# SCH_Freematics_ONE.net
KiCad netlist of a schematic drawn in Altium Designer
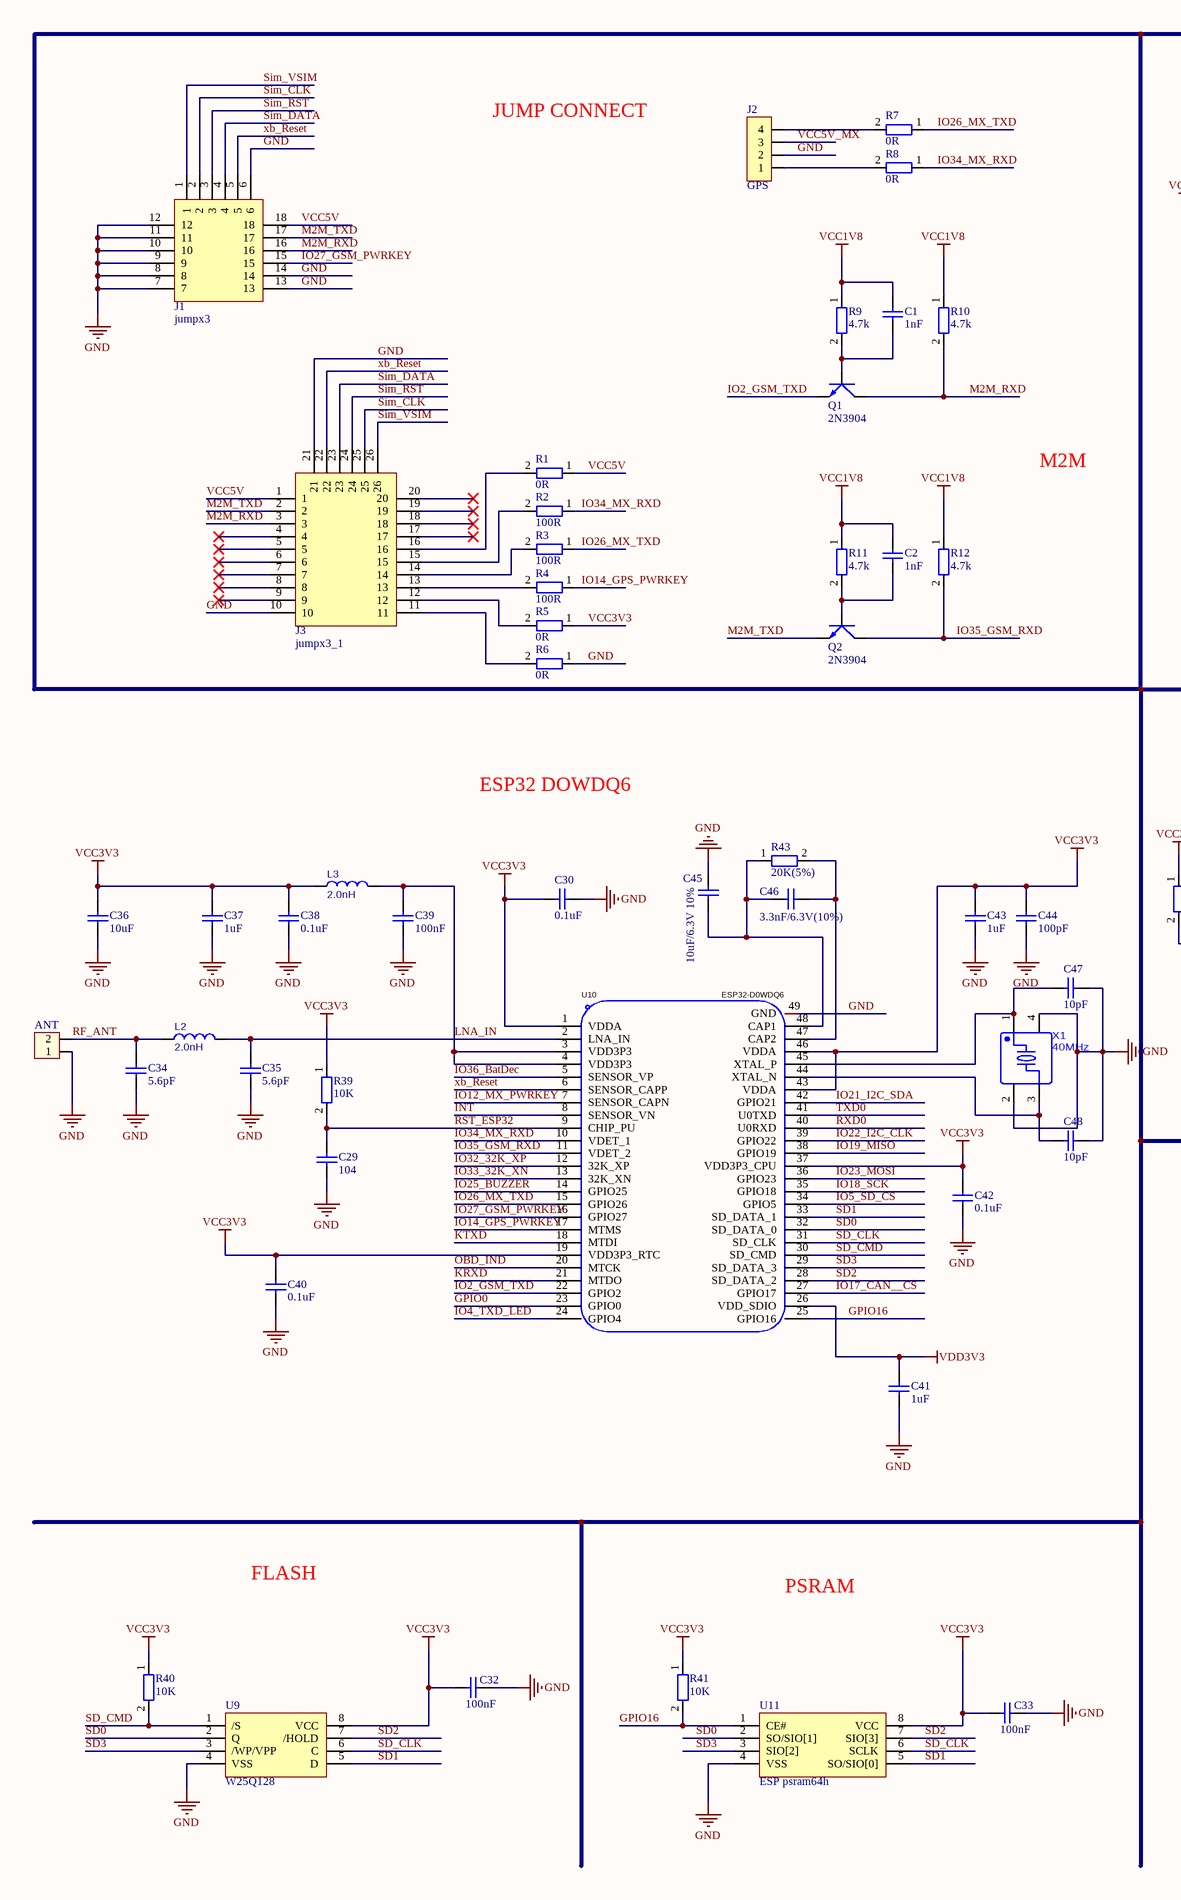
[diagram p0: SCH_Freematics_ONE.SchDoc, left]
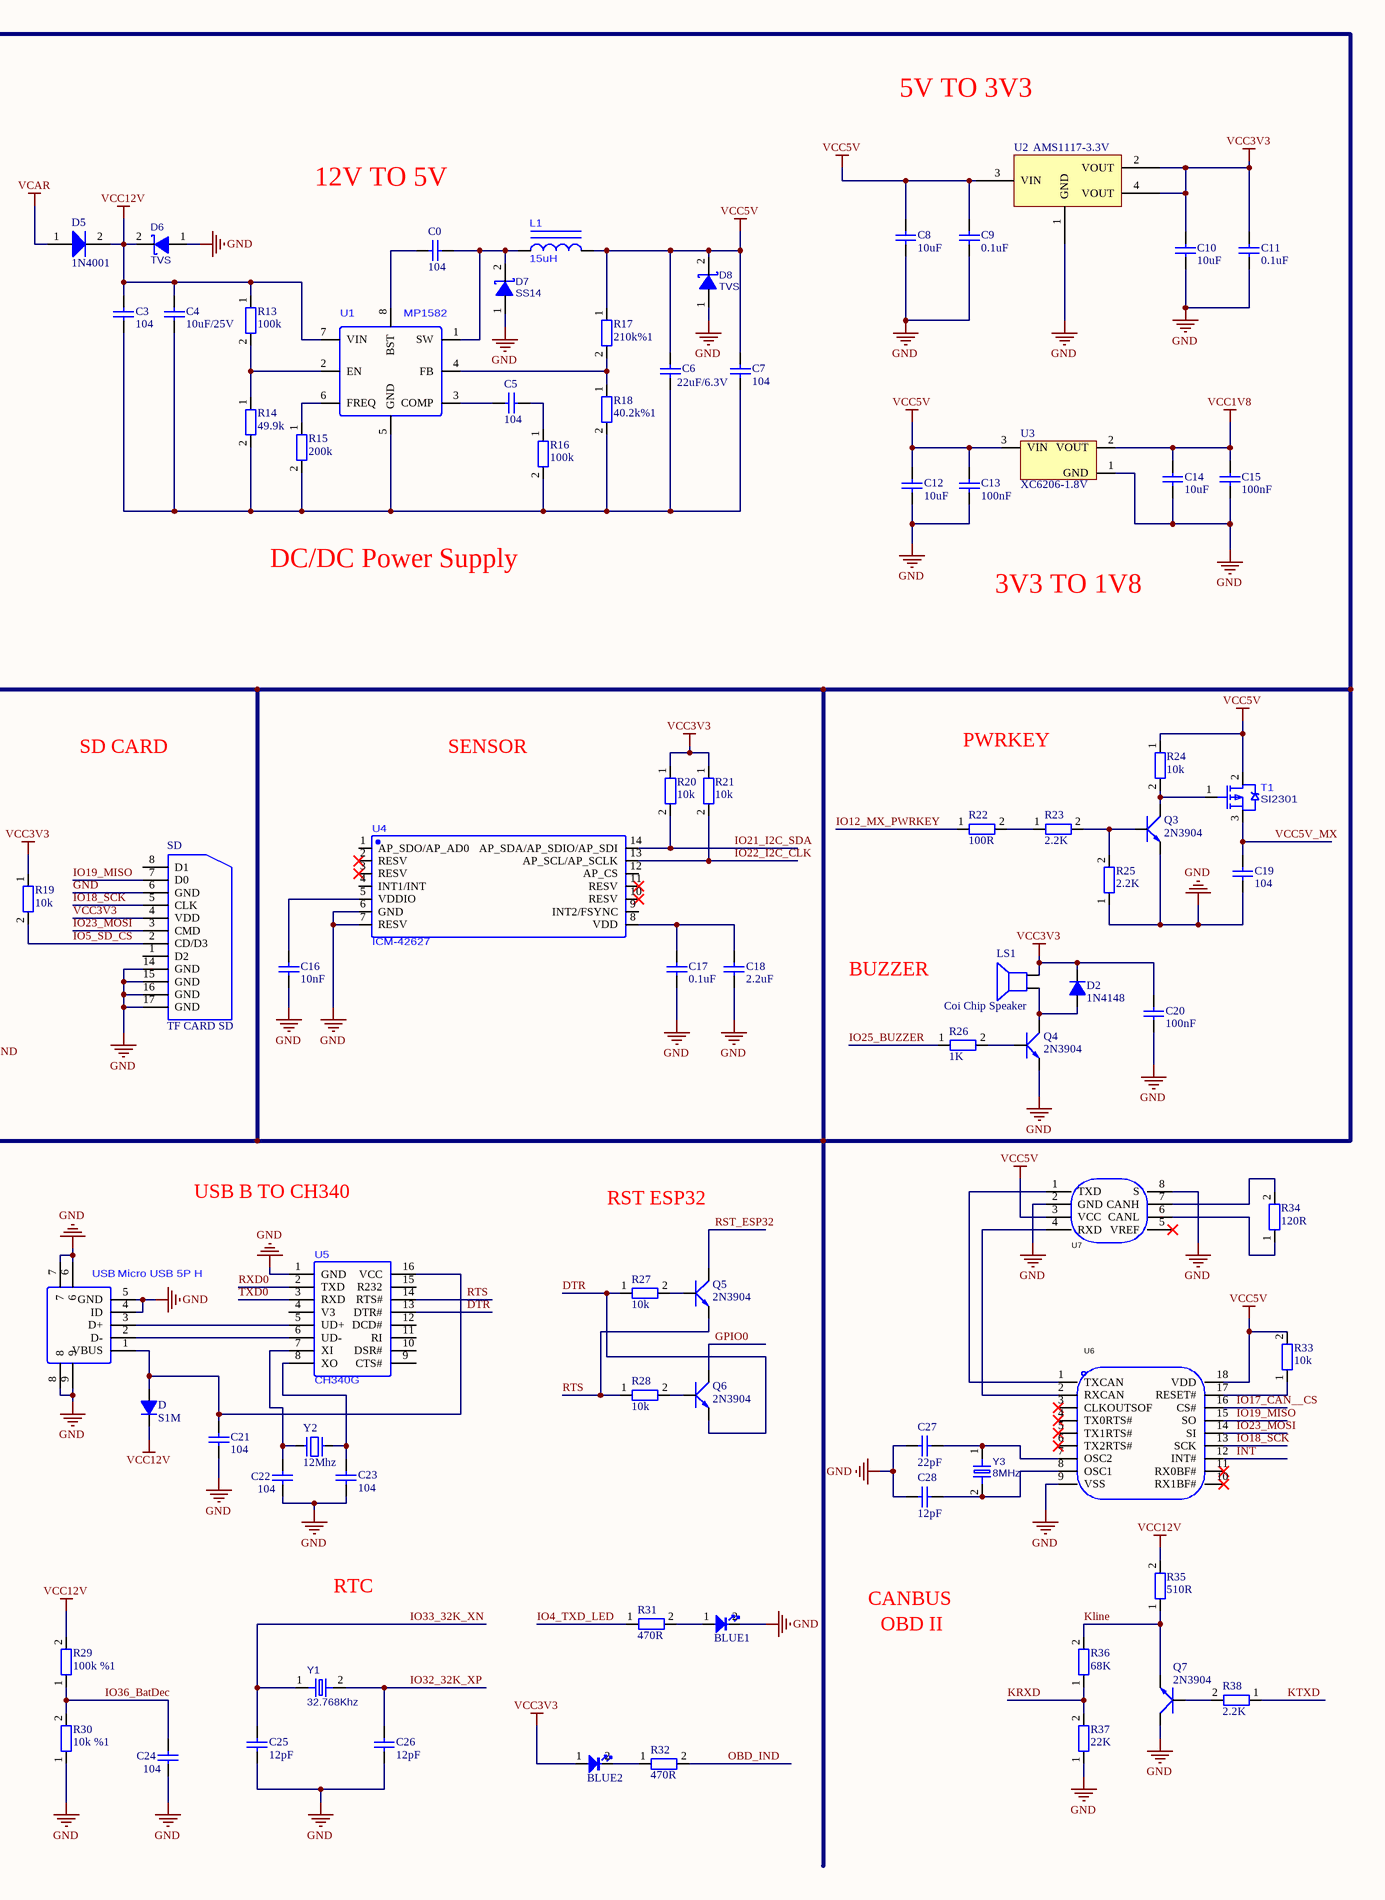
[diagram p1: SCH_Freematics_ONE.SchDoc, right]

(export (version "E")
  (design (tool "Eeschema 10.0.6"))
  (components
    (comp (ref "ANT")
      (value "Header 2")
      (footprint "HED2T")
      (description "Header 2 (Green)")
      (libsource (lib "SCH_Library") (part "Hed2"))
    )
    (comp (ref "BLUE1")
      (value "LED")
      (footprint "LED 0603")
      (description "Emerald 0603 Light Emitting Diodes (LED) ROHS")
      (libsource (lib "SCH_Library") (part "LED SMD 0603"))
    )
    (comp (ref "BLUE2")
      (value "LED")
      (footprint "LED 0603")
      (description "Emerald 0603 Light Emitting Diodes (LED) ROHS")
      (libsource (lib "SCH_Library") (part "LED SMD 0603"))
    )
    (comp (ref "C0")
      (value "104")
      (footprint "CAP0201")
      (description "Capacitor")
      (libsource (lib "SCH_Library") (part "CAP104-100nF-50V"))
    )
    (comp (ref "C1")
      (value "1nF")
      (footprint "CAP0201")
      (description "Capacitor")
      (libsource (lib "SCH_Library") (part "CAP104-100nF-50V"))
    )
    (comp (ref "C2")
      (value "1nF")
      (footprint "CAP0201")
      (description "Capacitor")
      (libsource (lib "SCH_Library") (part "CAP104-100nF-50V"))
    )
    (comp (ref "C3")
      (value "104")
      (footprint "CAP0201")
      (description "Capacitor")
      (libsource (lib "SCH_Library") (part "CAP104-100nF-50V"))
    )
    (comp (ref "C4")
      (value "10uF/25V")
      (footprint "CAP0201")
      (description "Capacitor")
      (libsource (lib "SCH_Library") (part "CAP104-100nF-50V"))
    )
    (comp (ref "C5")
      (value "104")
      (footprint "CAP0201")
      (description "Capacitor")
      (libsource (lib "SCH_Library") (part "CAP104-100nF-50V"))
    )
    (comp (ref "C6")
      (value "22uF/6.3V")
      (footprint "CAP0201")
      (description "Capacitor")
      (libsource (lib "SCH_Library") (part "CAP104-100nF-50V"))
    )
    (comp (ref "C7")
      (value "104")
      (footprint "CAP0201")
      (description "Capacitor")
      (libsource (lib "SCH_Library") (part "CAP104-100nF-50V"))
    )
    (comp (ref "C8")
      (value "10uF")
      (footprint "CAP0201")
      (description "0805 Multilayer Ceramic Capacitors MLCC - SMD/SMT ROHS")
      (libsource (lib "SCH_AES_Library") (part "CAP 0805 50V 10%"))
    )
    (comp (ref "C9")
      (value "0.1uF")
      (footprint "CAP0201")
      (description "0805 Multilayer Ceramic Capacitors MLCC - SMD/SMT ROHS")
      (libsource (lib "SCH_AES_Library") (part "CAP 0805 50V 10%"))
    )
    (comp (ref "C10")
      (value "10uF")
      (footprint "CAP0201")
      (description "0805 Multilayer Ceramic Capacitors MLCC - SMD/SMT ROHS")
      (libsource (lib "SCH_AES_Library") (part "CAP 0805 50V 10%"))
    )
    (comp (ref "C11")
      (value "0.1uF")
      (footprint "CAP0201")
      (description "0805 Multilayer Ceramic Capacitors MLCC - SMD/SMT ROHS")
      (libsource (lib "SCH_AES_Library") (part "CAP 0805 50V 10%"))
    )
    (comp (ref "C12")
      (value "10uF")
      (footprint "CAP0201")
      (description "Capacitor")
      (libsource (lib "SCH_Library") (part "CAP104-100nF-50V"))
    )
    (comp (ref "C13")
      (value "100nF")
      (footprint "CAP0201")
      (description "Capacitor")
      (libsource (lib "SCH_Library") (part "CAP104-100nF-50V"))
    )
    (comp (ref "C14")
      (value "10uF")
      (footprint "CAP0201")
      (description "Capacitor")
      (libsource (lib "SCH_Library") (part "CAP104-100nF-50V"))
    )
    (comp (ref "C15")
      (value "100nF")
      (footprint "CAP0201")
      (description "Capacitor")
      (libsource (lib "SCH_Library") (part "CAP104-100nF-50V"))
    )
    (comp (ref "C16")
      (value "10nF")
      (footprint "CAP0201")
      (description "Capacitor")
      (libsource (lib "SCH_Library") (part "CAP104-100nF-50V"))
    )
    (comp (ref "C17")
      (value "0.1uF")
      (footprint "CAP0201")
      (description "Capacitor")
      (libsource (lib "SCH_Library") (part "CAP104-100nF-50V"))
    )
    (comp (ref "C18")
      (value "2.2uF")
      (footprint "CAP0201")
      (description "Capacitor")
      (libsource (lib "SCH_Library") (part "CAP104-100nF-50V"))
    )
    (comp (ref "C19")
      (value "104")
      (footprint "CAP0201")
      (description "Capacitor")
      (libsource (lib "SCH_Library") (part "CAP104-100nF-50V"))
    )
    (comp (ref "C20")
      (value "100nF")
      (footprint "CAP0201")
      (description "Capacitor")
      (libsource (lib "SCH_Library") (part "CAP104-100nF-50V"))
    )
    (comp (ref "C21")
      (value "104")
      (footprint "CAP0201")
      (description "Capacitor")
      (libsource (lib "SCH_Library") (part "CAP104-100nF-50V"))
    )
    (comp (ref "C22")
      (value "104")
      (footprint "CAP0201")
      (description "Capacitor")
      (libsource (lib "SCH_Library") (part "CAP104-100nF-50V"))
    )
    (comp (ref "C23")
      (value "104")
      (footprint "CAP0201")
      (description "Capacitor")
      (libsource (lib "SCH_Library") (part "CAP104-100nF-50V"))
    )
    (comp (ref "C24")
      (value "104")
      (footprint "CAP0201")
      (description "Capacitor")
      (libsource (lib "SCH_Library") (part "CAP104-100nF-50V"))
    )
    (comp (ref "C25")
      (value "12pF")
      (footprint "CAP0201")
      (description "Capacitor")
      (libsource (lib "SCH_Library") (part "CAP104-100nF-50V"))
    )
    (comp (ref "C26")
      (value "12pF")
      (footprint "CAP0201")
      (description "Capacitor")
      (libsource (lib "SCH_Library") (part "CAP104-100nF-50V"))
    )
    (comp (ref "C27")
      (value "22pF")
      (footprint "CAP0201")
      (description "Capacitor")
      (libsource (lib "SCH_Library") (part "CAP104-100nF-50V"))
    )
    (comp (ref "C28")
      (value "12pF")
      (footprint "CAP0201")
      (description "Capacitor")
      (libsource (lib "SCH_Library") (part "CAP104-100nF-50V"))
    )
    (comp (ref "C29")
      (value "104")
      (footprint "CAP0201")
      (description "Capacitor")
      (libsource (lib "SCH_Library") (part "CAP104-100nF-50V"))
    )
    (comp (ref "C30")
      (value "0.1uF")
      (footprint "CAP0201")
      (description "Capacitor")
      (libsource (lib "SCH_Library") (part "CAP104-100nF-50V"))
    )
    (comp (ref "C32")
      (value "100nF")
      (footprint "CAP0201")
      (description "Capacitor")
      (libsource (lib "SCH_Library") (part "CAP104-100nF-50V"))
    )
    (comp (ref "C33")
      (value "100nF")
      (footprint "CAP0201")
      (description "Capacitor")
      (libsource (lib "SCH_Library") (part "CAP104-100nF-50V"))
    )
    (comp (ref "C34")
      (value "5.6pF")
      (footprint "CAP0201")
      (description "Capacitor")
      (libsource (lib "SCH_Library") (part "CAP104-100nF-50V"))
    )
    (comp (ref "C35")
      (value "5.6pF")
      (footprint "CAP0201")
      (description "Capacitor")
      (libsource (lib "SCH_Library") (part "CAP104-100nF-50V"))
    )
    (comp (ref "C36")
      (value "10uF")
      (footprint "CAP0201")
      (description "Capacitor")
      (libsource (lib "SCH_Library") (part "CAP104-100nF-50V"))
    )
    (comp (ref "C37")
      (value "1uF")
      (footprint "CAP0201")
      (description "Capacitor")
      (libsource (lib "SCH_Library") (part "CAP104-100nF-50V"))
    )
    (comp (ref "C38")
      (value "0.1uF")
      (footprint "CAP0201")
      (description "Capacitor")
      (libsource (lib "SCH_Library") (part "CAP104-100nF-50V"))
    )
    (comp (ref "C39")
      (value "100nF")
      (footprint "CAP0201")
      (description "Capacitor")
      (libsource (lib "SCH_Library") (part "CAP104-100nF-50V"))
    )
    (comp (ref "C40")
      (value "0.1uF")
      (footprint "CAP0201")
      (description "Capacitor")
      (libsource (lib "SCH_Library") (part "CAP104-100nF-50V"))
    )
    (comp (ref "C41")
      (value "1uF")
      (footprint "CAP0201")
      (description "Capacitor")
      (libsource (lib "SCH_Library") (part "CAP104-100nF-50V"))
    )
    (comp (ref "C42")
      (value "0.1uF")
      (footprint "CAP0201")
      (description "Capacitor")
      (libsource (lib "SCH_Library") (part "CAP104-100nF-50V"))
    )
    (comp (ref "C43")
      (value "1uF")
      (footprint "CAP0201")
      (description "Capacitor")
      (libsource (lib "SCH_Library") (part "CAP104-100nF-50V"))
    )
    (comp (ref "C44")
      (value "100pF")
      (footprint "CAP0201")
      (description "Capacitor")
      (libsource (lib "SCH_Library") (part "CAP104-100nF-50V"))
    )
    (comp (ref "C45")
      (value "10uF/6.3V 10%")
      (footprint "CAP_0805")
      (description "Capacitor")
      (libsource (lib "SCH_Library") (part "CAP104-100nF-50V"))
    )
    (comp (ref "C46")
      (value "3.3nF/6.3V(10%)")
      (footprint "CAP0201")
      (description "Capacitor")
      (libsource (lib "SCH_Library") (part "CAP104-100nF-50V"))
    )
    (comp (ref "C47")
      (value "10pF")
      (footprint "CAP0201")
      (description "Capacitor")
      (libsource (lib "SCH_Library") (part "CAP104-100nF-50V"))
    )
    (comp (ref "C48")
      (value "10pF")
      (footprint "CAP0201")
      (description "Capacitor")
      (libsource (lib "SCH_Library") (part "CAP104-100nF-50V"))
    )
    (comp (ref "D")
      (value "S1M")
      (footprint "DIODE_M7_1N4007")
      (description "Diode 1A")
      (libsource (lib "SCH_Library") (part "1N5819W"))
    )
    (comp (ref "D2")
      (value "1N4148")
      (footprint "DIODE_M7_1N4007")
      (description "Diode 1A")
      (libsource (lib "SCH_Library") (part "D1A"))
    )
    (comp (ref "D5")
      (value "1N4001")
      (footprint "Diode HOLD STAND DO-41 TYPE 1A")
      (description "1A 1kV Diodes - General Purpose ROHS")
      (libsource (lib "SCH_Library") (part "DIODE SMD 1N4007"))
    )
    (comp (ref "D6")
      (value "TVS")
      (footprint "DO-214AC(SMA)")
      (description "500uA@40V 40V 550mV@5A 5A SMA(DO-214AC) Schottky Barrier Diodes (SBD) ROHS")
      (fields
        (field (name "BOM_SUPPLIER PART") "C478723")
        (field (name "BOM_MANUFACTURER PART") "SS34")
        (field (name "CONTRIBUTOR") "LCSC")
      )
      (libsource (lib "SCH_Library") (part "DIODE SMD SS54"))
    )
    (comp (ref "D7")
      (value "SS14")
      (footprint "DO-214AC(SMA)")
      (description "500uA@40V 40V 550mV@5A 5A SMA(DO-214AC) Schottky Barrier Diodes (SBD) ROHS")
      (fields
        (field (name "BOM_SUPPLIER PART") "C478723")
        (field (name "BOM_MANUFACTURER PART") "SS34")
        (field (name "CONTRIBUTOR") "LCSC")
      )
      (libsource (lib "SCH_Library") (part "DIODE SMD SS54"))
    )
    (comp (ref "D8")
      (value "TVS")
      (footprint "DO-214AC(SMA)")
      (description "500uA@40V 40V 550mV@5A 5A SMA(DO-214AC) Schottky Barrier Diodes (SBD) ROHS")
      (fields
        (field (name "BOM_SUPPLIER PART") "C478723")
        (field (name "BOM_MANUFACTURER PART") "SS34")
        (field (name "CONTRIBUTOR") "LCSC")
      )
      (libsource (lib "SCH_Library") (part "DIODE SMD SS54"))
    )
    (comp (ref "J1") (value "jumpx3") (libsource (lib "SCH_Library") (part "jumpx3")))
    (comp (ref "J2")
      (value "GPS")
      (footprint "JP 1x4 DT")
      (description "Cắm")
      (libsource (lib "Altium_Lib") (part "JP 1x4 2.54 Duc Thang"))
    )
    (comp (ref "J3") (value "jumpx3_1") (libsource (lib "SCH_Library") (part "jumpx3_1")))
    (comp (ref "L1") (value "15uH") (libsource (lib "SCH_Library") (part "Inductor")))
    (comp (ref "L2")
      (value "2.0nH")
      (footprint "INDUCTOR_0201")
      (fields
        (field (name "BOM_SUPPLIER PART") "C578001")
        (field (name "BOM_MANUFACTURER PART") "SCHF160808H47NJT")
        (field (name "CONTRIBUTOR") "LCSC")
      )
      (libsource (lib "SCH_Library") (part "INDUCTORS SMD"))
    )
    (comp (ref "L3")
      (value "2.0nH")
      (footprint "INDUCTOR_0201")
      (fields
        (field (name "BOM_SUPPLIER PART") "C578001")
        (field (name "BOM_MANUFACTURER PART") "SCHF160808H47NJT")
        (field (name "CONTRIBUTOR") "LCSC")
      )
      (libsource (lib "SCH_Library") (part "INDUCTORS SMD"))
    )
    (comp (ref "LS1")
      (value "Coi Chip Speaker")
      (footprint "Coi Chip Speacker")
      (description "Còi chip")
      (libsource (lib "SCH_Library") (part "Coi Chip Speaker"))
    )
    (comp (ref "Q1")
      (value "2N3904")
      (footprint "SOT-23")
      (description "SOT-23 - C8658")
      (libsource (lib "Altium_Lib") (part "Trans BC817"))
    )
    (comp (ref "Q2")
      (value "2N3904")
      (footprint "SOT-23")
      (description "SOT-23 - C8658")
      (libsource (lib "Altium_Lib") (part "Trans BC817"))
    )
    (comp (ref "Q3")
      (value "2N3904")
      (footprint "SOT-23")
      (description "SOT-23 - C8658")
      (libsource (lib "Altium_Lib") (part "Trans BC817"))
    )
    (comp (ref "Q4")
      (value "2N3904")
      (footprint "SOT-23")
      (description "SOT-23 - C8658")
      (libsource (lib "Altium_Lib") (part "Trans BC817"))
    )
    (comp (ref "Q5")
      (value "2N3904")
      (footprint "SOT-23")
      (description "SOT-23 - C8658")
      (libsource (lib "Altium_Lib") (part "Trans BC817"))
    )
    (comp (ref "Q6")
      (value "2N3904")
      (footprint "SOT-23")
      (description "SOT-23 - C8658")
      (libsource (lib "Altium_Lib") (part "Trans BC817"))
    )
    (comp (ref "Q7")
      (value "2N3904")
      (footprint "SOT-23")
      (description "SOT-23 - C8658")
      (libsource (lib "Altium_Lib") (part "Trans BC817"))
    )
    (comp (ref "R1")
      (value "0R")
      (footprint "RESC0201_L")
      (description "±1% - Chip Resistor - Surface Mount ROHS")
      (libsource (lib "SCH_Library") (part "RES 0603 1%_"))
    )
    (comp (ref "R2")
      (value "100R")
      (footprint "RESC0201_L")
      (description "±1% - Chip Resistor - Surface Mount ROHS")
      (libsource (lib "SCH_Library") (part "RES 0603 1%_"))
    )
    (comp (ref "R3")
      (value "100R")
      (footprint "RESC0201_L")
      (description "±1% - Chip Resistor - Surface Mount ROHS")
      (libsource (lib "SCH_Library") (part "RES 0603 1%_"))
    )
    (comp (ref "R4")
      (value "100R")
      (footprint "RESC0201_L")
      (description "±1% - Chip Resistor - Surface Mount ROHS")
      (libsource (lib "SCH_Library") (part "RES 0603 1%_"))
    )
    (comp (ref "R5")
      (value "0R")
      (footprint "RESC0201_L")
      (description "±1% - Chip Resistor - Surface Mount ROHS")
      (libsource (lib "SCH_Library") (part "RES 0603 1%_"))
    )
    (comp (ref "R6")
      (value "0R")
      (footprint "RESC0201_L")
      (description "±1% - Chip Resistor - Surface Mount ROHS")
      (libsource (lib "SCH_Library") (part "RES 0603 1%_"))
    )
    (comp (ref "R7")
      (value "0R")
      (footprint "RESC0201_L")
      (description "±1% - Chip Resistor - Surface Mount ROHS")
      (libsource (lib "SCH_Library") (part "RES 0603 1%_"))
    )
    (comp (ref "R8")
      (value "0R")
      (footprint "RESC0201_L")
      (description "±1% - Chip Resistor - Surface Mount ROHS")
      (libsource (lib "SCH_Library") (part "RES 0603 1%_"))
    )
    (comp (ref "R9")
      (value "4.7k")
      (footprint "RESC0201_L")
      (description "±1% - Chip Resistor - Surface Mount ROHS")
      (libsource (lib "SCH_Library") (part "RES 0603 1%_"))
    )
    (comp (ref "R10")
      (value "4.7k")
      (footprint "RESC0201_L")
      (description "±1% - Chip Resistor - Surface Mount ROHS")
      (libsource (lib "SCH_Library") (part "RES 0603 1%_"))
    )
    (comp (ref "R11")
      (value "4.7k")
      (footprint "RESC0201_L")
      (description "±1% - Chip Resistor - Surface Mount ROHS")
      (libsource (lib "SCH_Library") (part "RES 0603 1%_"))
    )
    (comp (ref "R12")
      (value "4.7k")
      (footprint "RESC0201_L")
      (description "±1% - Chip Resistor - Surface Mount ROHS")
      (libsource (lib "SCH_Library") (part "RES 0603 1%_"))
    )
    (comp (ref "R13")
      (value "100k")
      (footprint "RESC0201_L")
      (description "±1% - Chip Resistor - Surface Mount ROHS")
      (libsource (lib "SCH_Library") (part "RES 0603 1%_"))
    )
    (comp (ref "R14")
      (value "49.9k")
      (footprint "RESC0201_L")
      (description "±1% - Chip Resistor - Surface Mount ROHS")
      (libsource (lib "SCH_Library") (part "RES 0603 1%_"))
    )
    (comp (ref "R15")
      (value "200k")
      (footprint "RESC0201_L")
      (description "±1% - Chip Resistor - Surface Mount ROHS")
      (libsource (lib "SCH_Library") (part "RES 0603 1%_"))
    )
    (comp (ref "R16")
      (value "100k")
      (footprint "RESC0201_L")
      (description "±1% - Chip Resistor - Surface Mount ROHS")
      (libsource (lib "SCH_Library") (part "RES 0603 1%_"))
    )
    (comp (ref "R17")
      (value "210k%1")
      (footprint "RESC0201_L")
      (description "±1% - Chip Resistor - Surface Mount ROHS")
      (libsource (lib "SCH_Library") (part "RES 0603 1%_"))
    )
    (comp (ref "R18")
      (value "40.2k%1")
      (footprint "RESC0201_L")
      (description "±1% - Chip Resistor - Surface Mount ROHS")
      (libsource (lib "SCH_Library") (part "RES 0603 1%_"))
    )
    (comp (ref "R19")
      (value "10k")
      (footprint "RESC0201_L")
      (description "±1% - Chip Resistor - Surface Mount ROHS")
      (libsource (lib "SCH_Library") (part "RES 0603 1%_"))
    )
    (comp (ref "R20")
      (value "10k")
      (footprint "RESC0201_L")
      (description "±1% - Chip Resistor - Surface Mount ROHS")
      (libsource (lib "SCH_Library") (part "RES 0603 1%_"))
    )
    (comp (ref "R21")
      (value "10k")
      (footprint "RESC0201_L")
      (description "±1% - Chip Resistor - Surface Mount ROHS")
      (libsource (lib "SCH_Library") (part "RES 0603 1%_"))
    )
    (comp (ref "R22")
      (value "100R")
      (footprint "RESC0201_L")
      (description "±1% - Chip Resistor - Surface Mount ROHS")
      (libsource (lib "SCH_Library") (part "RES 0603 1%_"))
    )
    (comp (ref "R23")
      (value "2.2K")
      (footprint "RESC0201_L")
      (description "±1% - Chip Resistor - Surface Mount ROHS")
      (libsource (lib "SCH_Library") (part "RES 0603 1%_"))
    )
    (comp (ref "R24")
      (value "10k")
      (footprint "RESC0201_L")
      (description "±1% - Chip Resistor - Surface Mount ROHS")
      (libsource (lib "SCH_Library") (part "RES 0603 1%_"))
    )
    (comp (ref "R25")
      (value "2.2K")
      (footprint "RESC0201_L")
      (description "±1% - Chip Resistor - Surface Mount ROHS")
      (libsource (lib "SCH_Library") (part "RES 0603 1%_"))
    )
    (comp (ref "R26")
      (value "1K")
      (footprint "RESC0201_L")
      (description "±1% - Chip Resistor - Surface Mount ROHS")
      (libsource (lib "SCH_Library") (part "RES 0603 1%_"))
    )
    (comp (ref "R27")
      (value "10k")
      (footprint "RESC0201_L")
      (description "±1% - Chip Resistor - Surface Mount ROHS")
      (libsource (lib "SCH_Library") (part "RES 0603 1%_"))
    )
    (comp (ref "R28")
      (value "10k")
      (footprint "RESC0201_L")
      (description "±1% - Chip Resistor - Surface Mount ROHS")
      (libsource (lib "SCH_Library") (part "RES 0603 1%_"))
    )
    (comp (ref "R29")
      (value "100k %1")
      (footprint "RESC0201_L")
      (description "±1% - Chip Resistor - Surface Mount ROHS")
      (libsource (lib "SCH_Library") (part "RES 0603 1%_"))
    )
    (comp (ref "R30")
      (value "10k %1")
      (footprint "RESC0201_L")
      (description "±1% - Chip Resistor - Surface Mount ROHS")
      (libsource (lib "SCH_Library") (part "RES 0603 1%_"))
    )
    (comp (ref "R31")
      (value "470R")
      (footprint "RESC0201_L")
      (description "±1% - Chip Resistor - Surface Mount ROHS")
      (libsource (lib "SCH_Library") (part "RES 0603 1%_"))
    )
    (comp (ref "R32")
      (value "470R")
      (footprint "RESC0201_L")
      (description "±1% - Chip Resistor - Surface Mount ROHS")
      (libsource (lib "SCH_Library") (part "RES 0603 1%_"))
    )
    (comp (ref "R33")
      (value "10k")
      (footprint "RESC0201_L")
      (description "±1% - Chip Resistor - Surface Mount ROHS")
      (libsource (lib "SCH_Library") (part "RES 0603 1%_"))
    )
    (comp (ref "R34")
      (value "120R")
      (footprint "RESC0201_L")
      (description "±1% - Chip Resistor - Surface Mount ROHS")
      (libsource (lib "SCH_Library") (part "RES 0603 1%_"))
    )
    (comp (ref "R35")
      (value "510R")
      (footprint "RESC0201_L")
      (description "±1% - Chip Resistor - Surface Mount ROHS")
      (libsource (lib "SCH_Library") (part "RES 0603 1%_"))
    )
    (comp (ref "R36")
      (value "68K")
      (footprint "RESC0201_L")
      (description "±1% - Chip Resistor - Surface Mount ROHS")
      (libsource (lib "SCH_Library") (part "RES 0603 1%_"))
    )
    (comp (ref "R37")
      (value "22K")
      (footprint "RESC0201_L")
      (description "±1% - Chip Resistor - Surface Mount ROHS")
      (libsource (lib "SCH_Library") (part "RES 0603 1%_"))
    )
    (comp (ref "R38")
      (value "2.2K")
      (footprint "RESC0201_L")
      (description "±1% - Chip Resistor - Surface Mount ROHS")
      (libsource (lib "SCH_Library") (part "RES 0603 1%_"))
    )
    (comp (ref "R39")
      (value "10K")
      (footprint "RESC0201_L")
      (description "±1% - Chip Resistor - Surface Mount ROHS")
      (libsource (lib "SCH_Library") (part "RES 0603 1%_"))
    )
    (comp (ref "R40")
      (value "10K")
      (footprint "RESC0201_L")
      (description "±1% - Chip Resistor - Surface Mount ROHS")
      (libsource (lib "SCH_Library") (part "RES 0603 1%_"))
    )
    (comp (ref "R41")
      (value "10K")
      (footprint "RESC0201_L")
      (description "±1% - Chip Resistor - Surface Mount ROHS")
      (libsource (lib "SCH_Library") (part "RES 0603 1%_"))
    )
    (comp (ref "R43")
      (value "20K(5%)")
      (footprint "RESC0201_L")
      (description "±1% - Chip Resistor - Surface Mount ROHS")
      (libsource (lib "SCH_Library") (part "RES 0603 1%_"))
    )
    (comp (ref "SD")
      (value "TF CARD SD")
      (footprint "SD TF-SD")
      (libsource (lib "SCH_Library") (part "TF CARD SD"))
    )
    (comp (ref "T1")
      (value "SI2301")
      (footprint "TO-252-3")
      (description "100V 13A 66W 205mΩ P Channel MOSFETs ROHS")
      (libsource (lib "SCH_Library") (part "MOSFET"))
    )
    (comp (ref "U1")
      (value "MP1582")
      (footprint "SOIC-8_L4.9-W3.9-P1.27-LS6.0-BL-EP")
      (libsource (lib "SCH_Library") (part "MP1582"))
    )
    (comp (ref "U2")
      (value "AMS1117-3.3V")
      (footprint "SOT-223")
      (description "800mA 1.4V@(1A) Fixed 3.3V~3.3V Positive 1 18V SOT-223 Linear Voltage Regulators (LDO) ROHS")
      (libsource (lib "SCH_AES_Library") (part "POWER CONVERTERS AMS117-3V3"))
    )
    (comp (ref "U3")
      (value "XC6206-1.8V")
      (footprint "SOT-23")
      (libsource (lib "SCH_Library") (part "XC6206-1.8V"))
    )
    (comp (ref "U4")
      (value "ICM-42627")
      (footprint "LGA-14_L3.0-W2.5-P0.50-BL")
      (libsource (lib "SCH_Library") (part "ICM-42627"))
    )
    (comp (ref "U5") (value "CH340G") (footprint "CH340G") (libsource (lib "SCH_Library") (part "CH340G")))
    (comp (ref "U6")
      (value "MCP2515")
      (footprint "SOIC-18_L11.6-W7.5-P1.27-LS10.3-BL")
      (fields
        (field (name "MANUFACTURER") "MICROCHIP(美国微芯)")
        (field (name "MANUFACTURER PART") "MCP2515-I/SO")
      )
      (libsource (lib "SCH_Library") (part "MCP2515"))
    )
    (comp (ref "U7")
      (value "TJA1050T")
      (footprint "SOP-8")
      (fields (field (name "MANUFACTURER") "NXP(恩智浦)") (field (name "MANUFACTURER PART") "TJA1050T/CM,118"))
      (libsource (lib "SCH_Library") (part "TJA1050T"))
    )
    (comp (ref "U9") (value "W25Q128") (footprint "SOIC-8") (libsource (lib "SCH_Library") (part "W25Q128")))
    (comp (ref "U10")
      (value "ESP32-D0WDQ6")
      (footprint "QFN-48_L6.0-W6.0-P0.40-BL-EP3.8")
      (fields (field (name "MANUFACTURER") "ESPRESSIF(乐鑫)"))
      (libsource (lib "SCH_Library") (part "ESP32-D0WDQ6"))
    )
    (comp (ref "U11")
      (value "ESP psram64h")
      (footprint "SOP-8")
      (libsource (lib "SCH_Library") (part "ESP psram64h"))
    )
    (comp (ref "USB")
      (value "Micro USB 5P H")
      (footprint "MICRO-USB_MICRO-USB-30")
      (libsource (lib "SCH_Library") (part "Micro USB 5P H"))
    )
    (comp (ref "X1")
      (value "40MHz")
      (footprint "CRYSTAL 40MHZ WURTH")
      (libsource (lib "SCH_Library") (part "Crystal 40MHz"))
    )
    (comp (ref "Y1")
      (value "32.768Khz")
      (footprint "CRYSTALS SMD FC-135 TYPE 2P")
      (description "Crystals ROHS")
      (fields
        (field (name "BOM_SUPPLIER PART") "C295072")
        (field (name "BOM_MANUFACTURER PART") "XIHCELNANF-12MHZ")
        (field (name "CONTRIBUTOR") "LCSC")
      )
      (libsource (lib "SCH_Library") (part "CRYSTALS 2P"))
    )
    (comp (ref "Y2")
      (value "12Mhz")
      (footprint "CRYSTALS SMD FC-135 TYPE 2P")
      (description "Crystal For all Crystal 2pin.")
      (libsource (lib "Altium_Lib") (part "Thach Anh 2 chan SMD"))
    )
    (comp (ref "Y3")
      (value "8MHz")
      (footprint "CRYSTALS SMD FC-135 TYPE 2P")
      (description "Crystals ROHS")
      (fields
        (field (name "BOM_SUPPLIER PART") "C295072")
        (field (name "BOM_MANUFACTURER PART") "XIHCELNANF-12MHZ")
        (field (name "CONTRIBUTOR") "LCSC")
      )
      (libsource (lib "SCH_Library") (part "CRYSTALS 2P"))
    )
  )
  (nets
    (net (code "1") (name "/DTR") (class "Default")
      (node (ref "Q6") (pin "2") (pinfunction "E_2") (pintype "passive"))
      (node (ref "R27") (pin "1") (pinfunction "1_1") (pintype "passive"))
      (node (ref "U5") (pin "13") (pinfunction "DTR#_13") (pintype "passive"))
    )
    (net (code "2") (name "/GPIO0") (class "Default")
      (node (ref "Q6") (pin "3") (pinfunction "C_3") (pintype "passive"))
      (node (ref "U10") (pin "23") (pinfunction "GPIO0_23") (pintype "passive"))
    )
    (net (code "3") (name "/GPIO16") (class "Default")
      (node (ref "R41") (pin "2") (pinfunction "2_2") (pintype "passive"))
      (node (ref "U10") (pin "25") (pinfunction "GPIO16_25") (pintype "passive"))
      (node (ref "U11") (pin "1") (pinfunction "CE#_1") (pintype "passive"))
    )
    (net (code "4") (name "/INT") (class "Default")
      (node (ref "U10") (pin "8") (pinfunction "SENSOR_VN_8") (pintype "passive"))
      (node (ref "U6") (pin "12") (pinfunction "INT#_12") (pintype "passive"))
    )
    (net (code "5") (name "/IO2_GSM_TXD") (class "Default")
      (node (ref "Q1") (pin "2") (pinfunction "E_2") (pintype "passive"))
      (node (ref "U10") (pin "22") (pinfunction "GPIO2_22") (pintype "passive"))
    )
    (net (code "6") (name "/IO4_TXD_LED") (class "Default")
      (node (ref "R31") (pin "1") (pinfunction "1_1") (pintype "passive"))
      (node (ref "U10") (pin "24") (pinfunction "GPIO4_24") (pintype "passive"))
    )
    (net (code "7") (name "/IO5_SD_CS") (class "Default")
      (node (ref "R19") (pin "2") (pinfunction "2_2") (pintype "passive"))
      (node (ref "SD") (pin "2") (pinfunction "CD/D3_2") (pintype "passive"))
      (node (ref "U10") (pin "34") (pinfunction "GPIO5_34") (pintype "passive"))
    )
    (net (code "8") (name "/IO12_MX_PWRKEY") (class "Default")
      (node (ref "R22") (pin "1") (pinfunction "1_1") (pintype "passive"))
      (node (ref "U10") (pin "7") (pinfunction "SENSOR_CAPN_7") (pintype "passive"))
    )
    (net (code "9") (name "/IO14_GPS_PWRKEY") (class "Default")
      (node (ref "R4") (pin "1") (pinfunction "1_1") (pintype "passive"))
      (node (ref "U10") (pin "17") (pinfunction "MTMS_17") (pintype "passive"))
    )
    (net (code "10") (name "/IO17_CAN__CS") (class "Default")
      (node (ref "U10") (pin "27") (pinfunction "GPIO17_27") (pintype "passive"))
      (node (ref "U6") (pin "16") (pinfunction "CS#_16") (pintype "passive"))
    )
    (net (code "11") (name "/IO18_SCK") (class "Default")
      (node (ref "SD") (pin "5") (pinfunction "CLK_5") (pintype "passive"))
      (node (ref "U10") (pin "35") (pinfunction "GPIO18_35") (pintype "passive"))
      (node (ref "U6") (pin "13") (pinfunction "SCK_13") (pintype "passive"))
    )
    (net (code "12") (name "/IO19_MISO") (class "Default")
      (node (ref "SD") (pin "7") (pinfunction "D0_7") (pintype "passive"))
      (node (ref "U10") (pin "38") (pinfunction "GPIO19_38") (pintype "passive"))
      (node (ref "U6") (pin "15") (pinfunction "SO_15") (pintype "passive"))
    )
    (net (code "13") (name "/IO21_I2C_SDA") (class "Default")
      (node (ref "R20") (pin "2") (pinfunction "2_2") (pintype "passive"))
      (node (ref "U10") (pin "42") (pinfunction "GPIO21_42") (pintype "passive"))
      (node (ref "U4") (pin "14") (pinfunction "AP_SDA/AP_SDIO/AP_SDI_14") (pintype "passive"))
    )
    (net (code "14") (name "/IO22_I2C_CLK") (class "Default")
      (node (ref "R21") (pin "2") (pinfunction "2_2") (pintype "passive"))
      (node (ref "U10") (pin "39") (pinfunction "GPIO22_39") (pintype "passive"))
      (node (ref "U4") (pin "13") (pinfunction "AP_SCL/AP_SCLK_13") (pintype "passive"))
    )
    (net (code "15") (name "/IO23_MOSI") (class "Default")
      (node (ref "SD") (pin "3") (pinfunction "CMD_3") (pintype "passive"))
      (node (ref "U10") (pin "36") (pinfunction "GPIO23_36") (pintype "passive"))
      (node (ref "U6") (pin "14") (pinfunction "SI_14") (pintype "passive"))
    )
    (net (code "16") (name "/IO25_BUZZER") (class "Default")
      (node (ref "R26") (pin "1") (pinfunction "1_1") (pintype "passive"))
      (node (ref "U10") (pin "14") (pinfunction "GPIO25_14") (pintype "passive"))
    )
    (net (code "17") (name "/IO26_MX_TXD") (class "Default")
      (node (ref "R3") (pin "1") (pinfunction "1_1") (pintype "passive"))
      (node (ref "R7") (pin "1") (pinfunction "1_1") (pintype "passive"))
      (node (ref "U10") (pin "15") (pinfunction "GPIO26_15") (pintype "passive"))
    )
    (net (code "18") (name "/IO27_GSM_PWRKEY") (class "Default")
      (node (ref "J1") (pin "15") (pinfunction "15_15") (pintype "passive"))
      (node (ref "U10") (pin "16") (pinfunction "GPIO27_16") (pintype "passive"))
    )
    (net (code "19") (name "/IO32_32K_XP") (class "Default")
      (node (ref "C26") (pin "2") (pinfunction "2_2") (pintype "passive"))
      (node (ref "U10") (pin "12") (pinfunction "32K_XP_12") (pintype "passive"))
      (node (ref "Y1") (pin "2") (pinfunction "2_2") (pintype "passive"))
    )
    (net (code "20") (name "/IO33_32K_XN") (class "Default")
      (node (ref "C25") (pin "2") (pinfunction "2_2") (pintype "passive"))
      (node (ref "U10") (pin "13") (pinfunction "32K_XN_13") (pintype "passive"))
      (node (ref "Y1") (pin "1") (pinfunction "1_1") (pintype "passive"))
    )
    (net (code "21") (name "/IO34_MX_RXD") (class "Default")
      (node (ref "R2") (pin "1") (pinfunction "1_1") (pintype "passive"))
      (node (ref "R8") (pin "1") (pinfunction "1_1") (pintype "passive"))
      (node (ref "U10") (pin "10") (pinfunction "VDET_1_10") (pintype "passive"))
    )
    (net (code "22") (name "/IO35_GSM_RXD") (class "Default")
      (node (ref "Q2") (pin "3") (pinfunction "C_3") (pintype "passive"))
      (node (ref "R12") (pin "2") (pinfunction "2_2") (pintype "passive"))
      (node (ref "U10") (pin "11") (pinfunction "VDET_2_11") (pintype "passive"))
    )
    (net (code "23") (name "/IO36_BatDec") (class "Default")
      (node (ref "C24") (pin "2") (pinfunction "2_2") (pintype "passive"))
      (node (ref "R29") (pin "1") (pinfunction "1_1") (pintype "passive"))
      (node (ref "R30") (pin "2") (pinfunction "2_2") (pintype "passive"))
      (node (ref "U10") (pin "5") (pinfunction "SENSOR_VP_5") (pintype "passive"))
    )
    (net (code "24") (name "/KRXD") (class "Default")
      (node (ref "R36") (pin "1") (pinfunction "1_1") (pintype "passive"))
      (node (ref "R37") (pin "2") (pinfunction "2_2") (pintype "passive"))
      (node (ref "U10") (pin "21") (pinfunction "MTDO_21") (pintype "passive"))
    )
    (net (code "25") (name "/KTXD") (class "Default")
      (node (ref "R38") (pin "1") (pinfunction "1_1") (pintype "passive"))
      (node (ref "U10") (pin "18") (pinfunction "MTDI_18") (pintype "passive"))
    )
    (net (code "26") (name "/Kline") (class "Default")
      (node (ref "Q7") (pin "2") (pinfunction "E_2") (pintype "passive"))
      (node (ref "R35") (pin "1") (pinfunction "1_1") (pintype "passive"))
      (node (ref "R36") (pin "2") (pinfunction "2_2") (pintype "passive"))
    )
    (net (code "27") (name "/LNA_IN") (class "Default")
      (node (ref "C35") (pin "2") (pinfunction "2_2") (pintype "passive"))
      (node (ref "C39") (pin "2") (pinfunction "2_2") (pintype "passive"))
      (node (ref "L2") (pin "2") (pinfunction "2_2") (pintype "passive"))
      (node (ref "L3") (pin "2") (pinfunction "2_2") (pintype "passive"))
      (node (ref "U10") (pin "2") (pinfunction "LNA_IN_2") (pintype "passive"))
      (node (ref "U10") (pin "3") (pinfunction "VDD3P3_3") (pintype "passive"))
      (node (ref "U10") (pin "4") (pinfunction "VDD3P3_4") (pintype "passive"))
    )
    (net (code "28") (name "/M2M_RXD") (class "Default")
      (node (ref "J1") (pin "16") (pinfunction "16_16") (pintype "passive"))
      (node (ref "J3") (pin "3") (pinfunction "3_3") (pintype "passive"))
      (node (ref "Q1") (pin "3") (pinfunction "C_3") (pintype "passive"))
      (node (ref "R10") (pin "2") (pinfunction "2_2") (pintype "passive"))
    )
    (net (code "29") (name "/M2M_TXD") (class "Default")
      (node (ref "J1") (pin "17") (pinfunction "17_17") (pintype "passive"))
      (node (ref "J3") (pin "2") (pinfunction "2_2") (pintype "passive"))
      (node (ref "Q2") (pin "2") (pinfunction "E_2") (pintype "passive"))
    )
    (net (code "30") (name "/OBD_IND") (class "Default")
      (node (ref "R32") (pin "2") (pinfunction "2_2") (pintype "passive"))
      (node (ref "U10") (pin "20") (pinfunction "MTCK_20") (pintype "passive"))
    )
    (net (code "31") (name "/RF_ANT") (class "Default")
      (node (ref "ANT") (pin "2") (pinfunction "2_2") (pintype "passive"))
      (node (ref "C34") (pin "2") (pinfunction "2_2") (pintype "passive"))
      (node (ref "L2") (pin "1") (pinfunction "1_1") (pintype "passive"))
    )
    (net (code "32") (name "/RST_ESP32") (class "Default")
      (node (ref "C29") (pin "2") (pinfunction "2_2") (pintype "passive"))
      (node (ref "Q5") (pin "3") (pinfunction "C_3") (pintype "passive"))
      (node (ref "R39") (pin "2") (pinfunction "2_2") (pintype "passive"))
      (node (ref "U10") (pin "9") (pinfunction "CHIP_PU_9") (pintype "passive"))
    )
    (net (code "33") (name "/RTS") (class "Default")
      (node (ref "Q5") (pin "2") (pinfunction "E_2") (pintype "passive"))
      (node (ref "R28") (pin "1") (pinfunction "1_1") (pintype "passive"))
      (node (ref "U5") (pin "14") (pinfunction "RTS#_14") (pintype "passive"))
    )
    (net (code "34") (name "/RXD0") (class "Default")
      (node (ref "U10") (pin "40") (pinfunction "U0RXD_40") (pintype "passive"))
      (node (ref "U5") (pin "2") (pinfunction "TXD_2") (pintype "passive"))
    )
    (net (code "35") (name "/SD0") (class "Default")
      (node (ref "U10") (pin "32") (pinfunction "SD_DATA_0_32") (pintype "passive"))
      (node (ref "U11") (pin "2") (pinfunction "SO/SIO[1]_2") (pintype "passive"))
      (node (ref "U9") (pin "2") (pinfunction "Q_2") (pintype "passive"))
    )
    (net (code "36") (name "/SD1") (class "Default")
      (node (ref "U10") (pin "33") (pinfunction "SD_DATA_1_33") (pintype "passive"))
      (node (ref "U11") (pin "5") (pinfunction "SO/SIO[0]_5") (pintype "passive"))
      (node (ref "U9") (pin "5") (pinfunction "D_5") (pintype "passive"))
    )
    (net (code "37") (name "/SD2") (class "Default")
      (node (ref "U10") (pin "28") (pinfunction "SD_DATA_2_28") (pintype "passive"))
      (node (ref "U11") (pin "7") (pinfunction "SIO[3]_7") (pintype "passive"))
      (node (ref "U9") (pin "7") (pinfunction "/HOLD_7") (pintype "passive"))
    )
    (net (code "38") (name "/SD3") (class "Default")
      (node (ref "U10") (pin "29") (pinfunction "SD_DATA_3_29") (pintype "passive"))
      (node (ref "U11") (pin "3") (pinfunction "SIO[2]_3") (pintype "passive"))
      (node (ref "U9") (pin "3") (pinfunction "/WP/VPP_3") (pintype "passive"))
    )
    (net (code "39") (name "/SD_CLK") (class "Default")
      (node (ref "U10") (pin "31") (pinfunction "SD_CLK_31") (pintype "passive"))
      (node (ref "U11") (pin "6") (pinfunction "SCLK_6") (pintype "passive"))
      (node (ref "U9") (pin "6") (pinfunction "C_6") (pintype "passive"))
    )
    (net (code "40") (name "/SD_CMD") (class "Default")
      (node (ref "R40") (pin "2") (pinfunction "2_2") (pintype "passive"))
      (node (ref "U10") (pin "30") (pinfunction "SD_CMD_30") (pintype "passive"))
      (node (ref "U9") (pin "1") (pinfunction "/S_1") (pintype "passive"))
    )
    (net (code "41") (name "/Sim_CLK") (class "Default")
      (node (ref "J1") (pin "2") (pinfunction "2_2") (pintype "passive"))
      (node (ref "J3") (pin "25") (pinfunction "25_25") (pintype "passive"))
    )
    (net (code "42") (name "/Sim_DATA") (class "Default")
      (node (ref "J1") (pin "4") (pinfunction "4_4") (pintype "passive"))
      (node (ref "J3") (pin "23") (pinfunction "23_23") (pintype "passive"))
    )
    (net (code "43") (name "/Sim_RST") (class "Default")
      (node (ref "J1") (pin "3") (pinfunction "3_3") (pintype "passive"))
      (node (ref "J3") (pin "24") (pinfunction "24_24") (pintype "passive"))
    )
    (net (code "44") (name "/Sim_VSIM") (class "Default")
      (node (ref "J1") (pin "1") (pinfunction "1_1") (pintype "passive"))
      (node (ref "J3") (pin "26") (pinfunction "26_26") (pintype "passive"))
    )
    (net (code "45") (name "/TXD0") (class "Default")
      (node (ref "U10") (pin "41") (pinfunction "U0TXD_41") (pintype "passive"))
      (node (ref "U5") (pin "3") (pinfunction "RXD_3") (pintype "passive"))
    )
    (net (code "46") (name "/VCC5V_MX") (class "Default")
      (node (ref "C19") (pin "1") (pinfunction "1_1") (pintype "passive"))
      (node (ref "J2") (pin "3") (pinfunction "3_3") (pintype "passive"))
      (node (ref "T1") (pin "3") (pinfunction "S_3") (pintype "passive"))
    )
    (net (code "47") (name "/xb_Reset") (class "Default")
      (node (ref "J1") (pin "5") (pinfunction "5_5") (pintype "passive"))
      (node (ref "J3") (pin "22") (pinfunction "22_22") (pintype "passive"))
      (node (ref "U10") (pin "6") (pinfunction "SENSOR_CAPP_6") (pintype "passive"))
    )
    (net (code "48") (name "GND") (class "Default")
      (node (ref "ANT") (pin "1") (pinfunction "1_1") (pintype "passive"))
      (node (ref "BLUE1") (pin "2") (pinfunction "2_2") (pintype "passive"))
      (node (ref "C10") (pin "2") (pinfunction "2_2") (pintype "passive"))
      (node (ref "C11") (pin "2") (pinfunction "2_2") (pintype "passive"))
      (node (ref "C12") (pin "2") (pinfunction "2_2") (pintype "passive"))
      (node (ref "C13") (pin "2") (pinfunction "2_2") (pintype "passive"))
      (node (ref "C14") (pin "2") (pinfunction "2_2") (pintype "passive"))
      (node (ref "C15") (pin "2") (pinfunction "2_2") (pintype "passive"))
      (node (ref "C16") (pin "2") (pinfunction "2_2") (pintype "passive"))
      (node (ref "C17") (pin "2") (pinfunction "2_2") (pintype "passive"))
      (node (ref "C18") (pin "2") (pinfunction "2_2") (pintype "passive"))
      (node (ref "C19") (pin "2") (pinfunction "2_2") (pintype "passive"))
      (node (ref "C20") (pin "1") (pinfunction "1_1") (pintype "passive"))
      (node (ref "C21") (pin "1") (pinfunction "1_1") (pintype "passive"))
      (node (ref "C22") (pin "1") (pinfunction "1_1") (pintype "passive"))
      (node (ref "C23") (pin "1") (pinfunction "1_1") (pintype "passive"))
      (node (ref "C24") (pin "1") (pinfunction "1_1") (pintype "passive"))
      (node (ref "C25") (pin "1") (pinfunction "1_1") (pintype "passive"))
      (node (ref "C26") (pin "1") (pinfunction "1_1") (pintype "passive"))
      (node (ref "C27") (pin "1") (pinfunction "1_1") (pintype "passive"))
      (node (ref "C28") (pin "1") (pinfunction "1_1") (pintype "passive"))
      (node (ref "C29") (pin "1") (pinfunction "1_1") (pintype "passive"))
      (node (ref "C30") (pin "1") (pinfunction "1_1") (pintype "passive"))
      (node (ref "C32") (pin "1") (pinfunction "1_1") (pintype "passive"))
      (node (ref "C33") (pin "1") (pinfunction "1_1") (pintype "passive"))
      (node (ref "C34") (pin "1") (pinfunction "1_1") (pintype "passive"))
      (node (ref "C35") (pin "1") (pinfunction "1_1") (pintype "passive"))
      (node (ref "C36") (pin "1") (pinfunction "1_1") (pintype "passive"))
      (node (ref "C37") (pin "1") (pinfunction "1_1") (pintype "passive"))
      (node (ref "C38") (pin "1") (pinfunction "1_1") (pintype "passive"))
      (node (ref "C39") (pin "1") (pinfunction "1_1") (pintype "passive"))
      (node (ref "C40") (pin "1") (pinfunction "1_1") (pintype "passive"))
      (node (ref "C41") (pin "1") (pinfunction "1_1") (pintype "passive"))
      (node (ref "C42") (pin "1") (pinfunction "1_1") (pintype "passive"))
      (node (ref "C43") (pin "1") (pinfunction "1_1") (pintype "passive"))
      (node (ref "C44") (pin "1") (pinfunction "1_1") (pintype "passive"))
      (node (ref "C45") (pin "1") (pinfunction "1_1") (pintype "passive"))
      (node (ref "C47") (pin "1") (pinfunction "1_1") (pintype "passive"))
      (node (ref "C48") (pin "1") (pinfunction "1_1") (pintype "passive"))
      (node (ref "C8") (pin "2") (pinfunction "2_2") (pintype "passive"))
      (node (ref "C9") (pin "2") (pinfunction "2_2") (pintype "passive"))
      (node (ref "D6") (pin "1") (pinfunction "A_1") (pintype "passive"))
      (node (ref "D7") (pin "1") (pinfunction "A_1") (pintype "passive"))
      (node (ref "D8") (pin "1") (pinfunction "A_1") (pintype "passive"))
      (node (ref "J1") (pin "10") (pinfunction "10_10") (pintype "passive"))
      (node (ref "J1") (pin "11") (pinfunction "11_11") (pintype "passive"))
      (node (ref "J1") (pin "12") (pinfunction "12_12") (pintype "passive"))
      (node (ref "J1") (pin "13") (pinfunction "13_13") (pintype "passive"))
      (node (ref "J1") (pin "14") (pinfunction "14_14") (pintype "passive"))
      (node (ref "J1") (pin "6") (pinfunction "6_6") (pintype "passive"))
      (node (ref "J1") (pin "7") (pinfunction "7_7") (pintype "passive"))
      (node (ref "J1") (pin "8") (pinfunction "8_8") (pintype "passive"))
      (node (ref "J1") (pin "9") (pinfunction "9_9") (pintype "passive"))
      (node (ref "J2") (pin "2") (pinfunction "2_2") (pintype "passive"))
      (node (ref "J3") (pin "10") (pinfunction "10_10") (pintype "passive"))
      (node (ref "J3") (pin "21") (pinfunction "21_21") (pintype "passive"))
      (node (ref "Q3") (pin "2") (pinfunction "E_2") (pintype "passive"))
      (node (ref "Q4") (pin "2") (pinfunction "E_2") (pintype "passive"))
      (node (ref "Q7") (pin "3") (pinfunction "C_3") (pintype "passive"))
      (node (ref "R25") (pin "1") (pinfunction "1_1") (pintype "passive"))
      (node (ref "R30") (pin "1") (pinfunction "1_1") (pintype "passive"))
      (node (ref "R37") (pin "1") (pinfunction "1_1") (pintype "passive"))
      (node (ref "R6") (pin "1") (pinfunction "1_1") (pintype "passive"))
      (node (ref "SD") (pin "14") (pinfunction "GND_14") (pintype "passive"))
      (node (ref "SD") (pin "15") (pinfunction "GND_15") (pintype "passive"))
      (node (ref "SD") (pin "16") (pinfunction "GND_16") (pintype "passive"))
      (node (ref "SD") (pin "17") (pinfunction "GND_17") (pintype "passive"))
      (node (ref "SD") (pin "6") (pinfunction "GND_6") (pintype "passive"))
      (node (ref "U10") (pin "49") (pinfunction "GND_49") (pintype "passive"))
      (node (ref "U11") (pin "4") (pinfunction "VSS_4") (pintype "passive"))
      (node (ref "U2") (pin "1") (pinfunction "GND_1") (pintype "passive"))
      (node (ref "U3") (pin "1") (pinfunction "GND_1") (pintype "passive"))
      (node (ref "U4") (pin "6") (pinfunction "GND_6") (pintype "passive"))
      (node (ref "U4") (pin "7") (pinfunction "RESV_7") (pintype "passive"))
      (node (ref "U5") (pin "1") (pinfunction "GND_1") (pintype "passive"))
      (node (ref "U6") (pin "9") (pinfunction "VSS_9") (pintype "passive"))
      (node (ref "U7") (pin "2") (pinfunction "GND_2") (pintype "passive"))
      (node (ref "U7") (pin "8") (pinfunction "S_8") (pintype "passive"))
      (node (ref "U9") (pin "4") (pinfunction "VSS_4") (pintype "passive"))
      (node (ref "USB") (pin "4") (pinfunction "ID_4") (pintype "passive"))
      (node (ref "USB") (pin "5") (pinfunction "GND_5") (pintype "passive"))
      (node (ref "USB") (pin "6") (pinfunction "6_6") (pintype "passive"))
      (node (ref "USB") (pin "7") (pinfunction "7_7") (pintype "passive"))
      (node (ref "USB") (pin "8") (pinfunction "8_8") (pintype "passive"))
      (node (ref "USB") (pin "9") (pinfunction "9_9") (pintype "passive"))
      (node (ref "X1") (pin "2") (pinfunction "GND_2") (pintype "passive"))
      (node (ref "X1") (pin "4") (pinfunction "GND_4") (pintype "passive"))
    )
    (net (code "49") (name "Net-(BLUE1-Pad1)") (class "Default")
      (node (ref "BLUE1") (pin "1") (pinfunction "1_1") (pintype "passive"))
      (node (ref "R31") (pin "2") (pinfunction "2_2") (pintype "passive"))
    )
    (net (code "50") (name "Net-(BLUE2-Pad2)") (class "Default")
      (node (ref "BLUE2") (pin "2") (pinfunction "2_2") (pintype "passive"))
      (node (ref "R32") (pin "1") (pinfunction "1_1") (pintype "passive"))
    )
    (net (code "51") (name "Net-(C5-Pad2)") (class "Default")
      (node (ref "C5") (pin "2") (pinfunction "2_2") (pintype "passive"))
      (node (ref "R16") (pin "1") (pinfunction "1_1") (pintype "passive"))
    )
    (net (code "52") (name "Net-(D-A)") (class "Default")
      (node (ref "C21") (pin "2") (pinfunction "2_2") (pintype "passive"))
      (node (ref "D") (pin "1") (pinfunction "A_1") (pintype "passive"))
      (node (ref "U5") (pin "16") (pinfunction "VCC_16") (pintype "passive"))
      (node (ref "USB") (pin "1") (pinfunction "VBUS_1") (pintype "passive"))
    )
    (net (code "53") (name "Net-(D2-A)") (class "Default")
      (node (ref "D2") (pin "1") (pinfunction "A_1") (pintype "passive"))
      (node (ref "LS1") (pin "1") (pinfunction "1_1") (pintype "passive"))
      (node (ref "Q4") (pin "3") (pinfunction "C_3") (pintype "passive"))
    )
    (net (code "54") (name "Net-(D7-K)") (class "Default")
      (node (ref "C0") (pin "1") (pinfunction "1_1") (pintype "passive"))
      (node (ref "D7") (pin "2") (pinfunction "K_2") (pintype "passive"))
      (node (ref "L1") (pin "1") (pinfunction "1_1") (pintype "passive"))
      (node (ref "U1") (pin "1") (pinfunction "SW_1") (pintype "passive"))
    )
    (net (code "55") (name "Net-(J2-Pad1)") (class "Default")
      (node (ref "J2") (pin "1") (pinfunction "1_1") (pintype "passive"))
      (node (ref "R8") (pin "2") (pinfunction "2_2") (pintype "passive"))
    )
    (net (code "56") (name "Net-(J2-Pad4)") (class "Default")
      (node (ref "J2") (pin "4") (pinfunction "4_4") (pintype "passive"))
      (node (ref "R7") (pin "2") (pinfunction "2_2") (pintype "passive"))
    )
    (net (code "57") (name "Net-(J3-Pad11)") (class "Default")
      (node (ref "J3") (pin "11") (pinfunction "11_11") (pintype "passive"))
      (node (ref "R6") (pin "2") (pinfunction "2_2") (pintype "passive"))
    )
    (net (code "58") (name "Net-(J3-Pad12)") (class "Default")
      (node (ref "J3") (pin "12") (pinfunction "12_12") (pintype "passive"))
      (node (ref "R5") (pin "2") (pinfunction "2_2") (pintype "passive"))
    )
    (net (code "59") (name "Net-(J3-Pad13)") (class "Default")
      (node (ref "J3") (pin "13") (pinfunction "13_13") (pintype "passive"))
      (node (ref "R4") (pin "2") (pinfunction "2_2") (pintype "passive"))
    )
    (net (code "60") (name "Net-(J3-Pad14)") (class "Default")
      (node (ref "J3") (pin "14") (pinfunction "14_14") (pintype "passive"))
      (node (ref "R3") (pin "2") (pinfunction "2_2") (pintype "passive"))
    )
    (net (code "61") (name "Net-(J3-Pad15)") (class "Default")
      (node (ref "J3") (pin "15") (pinfunction "15_15") (pintype "passive"))
      (node (ref "R2") (pin "2") (pinfunction "2_2") (pintype "passive"))
    )
    (net (code "62") (name "Net-(J3-Pad16)") (class "Default")
      (node (ref "J3") (pin "16") (pinfunction "16_16") (pintype "passive"))
      (node (ref "R1") (pin "2") (pinfunction "2_2") (pintype "passive"))
    )
    (net (code "63") (name "Net-(Q1-B)") (class "Default")
      (node (ref "C1") (pin "1") (pinfunction "1_1") (pintype "passive"))
      (node (ref "Q1") (pin "1") (pinfunction "B_1") (pintype "passive"))
      (node (ref "R9") (pin "2") (pinfunction "2_2") (pintype "passive"))
    )
    (net (code "64") (name "Net-(Q2-B)") (class "Default")
      (node (ref "C2") (pin "1") (pinfunction "1_1") (pintype "passive"))
      (node (ref "Q2") (pin "1") (pinfunction "B_1") (pintype "passive"))
      (node (ref "R11") (pin "2") (pinfunction "2_2") (pintype "passive"))
    )
    (net (code "65") (name "Net-(Q3-B)") (class "Default")
      (node (ref "Q3") (pin "1") (pinfunction "B_1") (pintype "passive"))
      (node (ref "R23") (pin "2") (pinfunction "2_2") (pintype "passive"))
      (node (ref "R25") (pin "2") (pinfunction "2_2") (pintype "passive"))
    )
    (net (code "66") (name "Net-(Q3-C)") (class "Default")
      (node (ref "Q3") (pin "3") (pinfunction "C_3") (pintype "passive"))
      (node (ref "R24") (pin "2") (pinfunction "2_2") (pintype "passive"))
      (node (ref "T1") (pin "1") (pinfunction "G_1") (pintype "passive"))
    )
    (net (code "67") (name "Net-(Q4-B)") (class "Default")
      (node (ref "Q4") (pin "1") (pinfunction "B_1") (pintype "passive"))
      (node (ref "R26") (pin "2") (pinfunction "2_2") (pintype "passive"))
    )
    (net (code "68") (name "Net-(Q5-B)") (class "Default")
      (node (ref "Q5") (pin "1") (pinfunction "B_1") (pintype "passive"))
      (node (ref "R27") (pin "2") (pinfunction "2_2") (pintype "passive"))
    )
    (net (code "69") (name "Net-(Q6-B)") (class "Default")
      (node (ref "Q6") (pin "1") (pinfunction "B_1") (pintype "passive"))
      (node (ref "R28") (pin "2") (pinfunction "2_2") (pintype "passive"))
    )
    (net (code "70") (name "Net-(Q7-B)") (class "Default")
      (node (ref "Q7") (pin "1") (pinfunction "B_1") (pintype "passive"))
      (node (ref "R38") (pin "2") (pinfunction "2_2") (pintype "passive"))
    )
    (net (code "71") (name "Net-(R22-Pad2)") (class "Default")
      (node (ref "R22") (pin "2") (pinfunction "2_2") (pintype "passive"))
      (node (ref "R23") (pin "1") (pinfunction "1_1") (pintype "passive"))
    )
    (net (code "72") (name "Net-(U1-BST)") (class "Default")
      (node (ref "C0") (pin "2") (pinfunction "2_2") (pintype "passive"))
      (node (ref "U1") (pin "8") (pinfunction "BST_8") (pintype "passive"))
    )
    (net (code "73") (name "Net-(U1-COMP)") (class "Default")
      (node (ref "C5") (pin "1") (pinfunction "1_1") (pintype "passive"))
      (node (ref "U1") (pin "3") (pinfunction "COMP_3") (pintype "passive"))
    )
    (net (code "74") (name "Net-(U1-EN)") (class "Default")
      (node (ref "R13") (pin "2") (pinfunction "2_2") (pintype "passive"))
      (node (ref "R14") (pin "1") (pinfunction "1_1") (pintype "passive"))
      (node (ref "U1") (pin "2") (pinfunction "EN_2") (pintype "passive"))
    )
    (net (code "75") (name "Net-(U1-FB)") (class "Default")
      (node (ref "R17") (pin "2") (pinfunction "2_2") (pintype "passive"))
      (node (ref "R18") (pin "1") (pinfunction "1_1") (pintype "passive"))
      (node (ref "U1") (pin "4") (pinfunction "FB_4") (pintype "passive"))
    )
    (net (code "76") (name "Net-(U1-FREQ)") (class "Default")
      (node (ref "R15") (pin "1") (pinfunction "1_1") (pintype "passive"))
      (node (ref "U1") (pin "6") (pinfunction "FREQ_6") (pintype "passive"))
    )
    (net (code "77") (name "Net-(U1-GND)") (class "Default")
      (node (ref "C3") (pin "1") (pinfunction "1_1") (pintype "passive"))
      (node (ref "C4") (pin "1") (pinfunction "1_1") (pintype "passive"))
      (node (ref "C6") (pin "2") (pinfunction "2_2") (pintype "passive"))
      (node (ref "C7") (pin "2") (pinfunction "2_2") (pintype "passive"))
      (node (ref "R14") (pin "2") (pinfunction "2_2") (pintype "passive"))
      (node (ref "R15") (pin "2") (pinfunction "2_2") (pintype "passive"))
      (node (ref "R16") (pin "2") (pinfunction "2_2") (pintype "passive"))
      (node (ref "R18") (pin "2") (pinfunction "2_2") (pintype "passive"))
      (node (ref "U1") (pin "5") (pinfunction "GND_5") (pintype "passive"))
    )
    (net (code "78") (name "Net-(U4-VDD)") (class "Default")
      (node (ref "C17") (pin "1") (pinfunction "1_1") (pintype "passive"))
      (node (ref "C18") (pin "1") (pinfunction "1_1") (pintype "passive"))
      (node (ref "U4") (pin "8") (pinfunction "VDD_8") (pintype "passive"))
    )
    (net (code "79") (name "Net-(U4-VDDIO)") (class "Default")
      (node (ref "C16") (pin "1") (pinfunction "1_1") (pintype "passive"))
      (node (ref "U4") (pin "5") (pinfunction "VDDIO_5") (pintype "passive"))
    )
    (net (code "80") (name "Net-(U5-UD+)") (class "Default")
      (node (ref "U5") (pin "5") (pinfunction "UD+_5") (pintype "passive"))
      (node (ref "USB") (pin "3") (pinfunction "D+_3") (pintype "passive"))
    )
    (net (code "81") (name "Net-(U5-UD-)") (class "Default")
      (node (ref "U5") (pin "6") (pinfunction "UD-_6") (pintype "passive"))
      (node (ref "USB") (pin "2") (pinfunction "D-_2") (pintype "passive"))
    )
    (net (code "82") (name "Net-(U5-XI)") (class "Default")
      (node (ref "C22") (pin "2") (pinfunction "2_2") (pintype "passive"))
      (node (ref "U5") (pin "7") (pinfunction "XI_7") (pintype "passive"))
      (node (ref "Y2") (pin "1") (pinfunction "1_1") (pintype "passive"))
    )
    (net (code "83") (name "Net-(U5-XO)") (class "Default")
      (node (ref "C23") (pin "2") (pinfunction "2_2") (pintype "passive"))
      (node (ref "U5") (pin "8") (pinfunction "XO_8") (pintype "passive"))
      (node (ref "Y2") (pin "2") (pinfunction "2_2") (pintype "passive"))
    )
    (net (code "84") (name "Net-(U6-OSC1)") (class "Default")
      (node (ref "C28") (pin "2") (pinfunction "2_2") (pintype "passive"))
      (node (ref "U6") (pin "8") (pinfunction "OSC1_8") (pintype "passive"))
      (node (ref "Y3") (pin "2") (pinfunction "2_2") (pintype "passive"))
    )
    (net (code "85") (name "Net-(U6-OSC2)") (class "Default")
      (node (ref "C27") (pin "2") (pinfunction "2_2") (pintype "passive"))
      (node (ref "U6") (pin "7") (pinfunction "OSC2_7") (pintype "passive"))
      (node (ref "Y3") (pin "1") (pinfunction "1_1") (pintype "passive"))
    )
    (net (code "86") (name "Net-(U6-RESET#)") (class "Default")
      (node (ref "R33") (pin "1") (pinfunction "1_1") (pintype "passive"))
      (node (ref "U6") (pin "17") (pinfunction "RESET#_17") (pintype "passive"))
    )
    (net (code "87") (name "Net-(U6-RXCAN)") (class "Default")
      (node (ref "U6") (pin "2") (pinfunction "RXCAN_2") (pintype "passive"))
      (node (ref "U7") (pin "4") (pinfunction "RXD_4") (pintype "passive"))
    )
    (net (code "88") (name "Net-(U6-TXCAN)") (class "Default")
      (node (ref "U6") (pin "1") (pinfunction "TXCAN_1") (pintype "passive"))
      (node (ref "U7") (pin "1") (pinfunction "TXD_1") (pintype "passive"))
    )
    (net (code "89") (name "Net-(U7-CANH)") (class "Default")
      (node (ref "R34") (pin "2") (pinfunction "2_2") (pintype "passive"))
      (node (ref "U7") (pin "7") (pinfunction "CANH_7") (pintype "passive"))
    )
    (net (code "90") (name "Net-(U7-CANL)") (class "Default")
      (node (ref "R34") (pin "1") (pinfunction "1_1") (pintype "passive"))
      (node (ref "U7") (pin "6") (pinfunction "CANL_6") (pintype "passive"))
    )
    (net (code "91") (name "Net-(U10-CAP1)") (class "Default")
      (node (ref "C45") (pin "2") (pinfunction "2_2") (pintype "passive"))
      (node (ref "C46") (pin "2") (pinfunction "2_2") (pintype "passive"))
      (node (ref "R43") (pin "1") (pinfunction "1_1") (pintype "passive"))
      (node (ref "U10") (pin "48") (pinfunction "CAP1_48") (pintype "passive"))
    )
    (net (code "92") (name "Net-(U10-CAP2)") (class "Default")
      (node (ref "C46") (pin "1") (pinfunction "1_1") (pintype "passive"))
      (node (ref "R43") (pin "2") (pinfunction "2_2") (pintype "passive"))
      (node (ref "U10") (pin "47") (pinfunction "CAP2_47") (pintype "passive"))
    )
    (net (code "93") (name "Net-(U10-XTAL_N)") (class "Default")
      (node (ref "C48") (pin "2") (pinfunction "2_2") (pintype "passive"))
      (node (ref "U10") (pin "44") (pinfunction "XTAL_N_44") (pintype "passive"))
      (node (ref "X1") (pin "3") (pinfunction "3_3") (pintype "passive"))
    )
    (net (code "94") (name "Net-(U10-XTAL_P)") (class "Default")
      (node (ref "C47") (pin "2") (pinfunction "2_2") (pintype "passive"))
      (node (ref "U10") (pin "45") (pinfunction "XTAL_P_45") (pintype "passive"))
      (node (ref "X1") (pin "1") (pinfunction "1_1") (pintype "passive"))
    )
    (net (code "95") (name "VCAR") (class "Default")
      (node (ref "D5") (pin "1") (pinfunction "A_1") (pintype "passive"))
    )
    (net (code "96") (name "VCC1V8") (class "Default")
      (node (ref "C1") (pin "2") (pinfunction "2_2") (pintype "passive"))
      (node (ref "C14") (pin "1") (pinfunction "1_1") (pintype "passive"))
      (node (ref "C15") (pin "1") (pinfunction "1_1") (pintype "passive"))
      (node (ref "C2") (pin "2") (pinfunction "2_2") (pintype "passive"))
      (node (ref "R10") (pin "1") (pinfunction "1_1") (pintype "passive"))
      (node (ref "R11") (pin "1") (pinfunction "1_1") (pintype "passive"))
      (node (ref "R12") (pin "1") (pinfunction "1_1") (pintype "passive"))
      (node (ref "R9") (pin "1") (pinfunction "1_1") (pintype "passive"))
      (node (ref "U3") (pin "2") (pinfunction "VOUT_2") (pintype "passive"))
    )
    (net (code "97") (name "VCC3V3") (class "Default")
      (node (ref "BLUE2") (pin "1") (pinfunction "1_1") (pintype "passive"))
      (node (ref "C10") (pin "1") (pinfunction "1_1") (pintype "passive"))
      (node (ref "C11") (pin "1") (pinfunction "1_1") (pintype "passive"))
      (node (ref "C20") (pin "2") (pinfunction "2_2") (pintype "passive"))
      (node (ref "C30") (pin "2") (pinfunction "2_2") (pintype "passive"))
      (node (ref "C32") (pin "2") (pinfunction "2_2") (pintype "passive"))
      (node (ref "C33") (pin "2") (pinfunction "2_2") (pintype "passive"))
      (node (ref "C36") (pin "2") (pinfunction "2_2") (pintype "passive"))
      (node (ref "C37") (pin "2") (pinfunction "2_2") (pintype "passive"))
      (node (ref "C38") (pin "2") (pinfunction "2_2") (pintype "passive"))
      (node (ref "C40") (pin "2") (pinfunction "2_2") (pintype "passive"))
      (node (ref "C42") (pin "2") (pinfunction "2_2") (pintype "passive"))
      (node (ref "C43") (pin "2") (pinfunction "2_2") (pintype "passive"))
      (node (ref "C44") (pin "2") (pinfunction "2_2") (pintype "passive"))
      (node (ref "D2") (pin "2") (pinfunction "K_2") (pintype "passive"))
      (node (ref "L3") (pin "1") (pinfunction "1_1") (pintype "passive"))
      (node (ref "LS1") (pin "2") (pinfunction "2_2") (pintype "passive"))
      (node (ref "R19") (pin "1") (pinfunction "1_1") (pintype "passive"))
      (node (ref "R20") (pin "1") (pinfunction "1_1") (pintype "passive"))
      (node (ref "R21") (pin "1") (pinfunction "1_1") (pintype "passive"))
      (node (ref "R39") (pin "1") (pinfunction "1_1") (pintype "passive"))
      (node (ref "R40") (pin "1") (pinfunction "1_1") (pintype "passive"))
      (node (ref "R41") (pin "1") (pinfunction "1_1") (pintype "passive"))
      (node (ref "R5") (pin "1") (pinfunction "1_1") (pintype "passive"))
      (node (ref "SD") (pin "4") (pinfunction "VDD_4") (pintype "passive"))
      (node (ref "U10") (pin "1") (pinfunction "VDDA_1") (pintype "passive"))
      (node (ref "U10") (pin "19") (pinfunction "VDD3P3_RTC_19") (pintype "passive"))
      (node (ref "U10") (pin "37") (pinfunction "VDD3P3_CPU_37") (pintype "passive"))
      (node (ref "U10") (pin "43") (pinfunction "VDDA_43") (pintype "passive"))
      (node (ref "U10") (pin "46") (pinfunction "VDDA_46") (pintype "passive"))
      (node (ref "U11") (pin "8") (pinfunction "VCC_8") (pintype "passive"))
      (node (ref "U2") (pin "2") (pinfunction "VOUT_2") (pintype "passive"))
      (node (ref "U2") (pin "4") (pinfunction "VOUT_4") (pintype "passive"))
      (node (ref "U9") (pin "8") (pinfunction "VCC_8") (pintype "passive"))
    )
    (net (code "98") (name "VCC5V") (class "Default")
      (node (ref "C12") (pin "1") (pinfunction "1_1") (pintype "passive"))
      (node (ref "C13") (pin "1") (pinfunction "1_1") (pintype "passive"))
      (node (ref "C6") (pin "1") (pinfunction "1_1") (pintype "passive"))
      (node (ref "C7") (pin "1") (pinfunction "1_1") (pintype "passive"))
      (node (ref "C8") (pin "1") (pinfunction "1_1") (pintype "passive"))
      (node (ref "C9") (pin "1") (pinfunction "1_1") (pintype "passive"))
      (node (ref "D8") (pin "2") (pinfunction "K_2") (pintype "passive"))
      (node (ref "J1") (pin "18") (pinfunction "18_18") (pintype "passive"))
      (node (ref "J3") (pin "1") (pinfunction "1_1") (pintype "passive"))
      (node (ref "L1") (pin "2") (pinfunction "2_2") (pintype "passive"))
      (node (ref "R1") (pin "1") (pinfunction "1_1") (pintype "passive"))
      (node (ref "R17") (pin "1") (pinfunction "1_1") (pintype "passive"))
      (node (ref "R24") (pin "1") (pinfunction "1_1") (pintype "passive"))
      (node (ref "R33") (pin "2") (pinfunction "2_2") (pintype "passive"))
      (node (ref "T1") (pin "2") (pinfunction "D_2") (pintype "passive"))
      (node (ref "U2") (pin "3") (pinfunction "VIN_3") (pintype "passive"))
      (node (ref "U3") (pin "3") (pinfunction "VIN_3") (pintype "passive"))
      (node (ref "U6") (pin "18") (pinfunction "VDD_18") (pintype "passive"))
      (node (ref "U7") (pin "3") (pinfunction "VCC_3") (pintype "passive"))
    )
    (net (code "99") (name "VCC12V") (class "Default")
      (node (ref "C3") (pin "2") (pinfunction "2_2") (pintype "passive"))
      (node (ref "C4") (pin "2") (pinfunction "2_2") (pintype "passive"))
      (node (ref "D") (pin "2") (pinfunction "K_2") (pintype "passive"))
      (node (ref "D5") (pin "2") (pinfunction "K_2") (pintype "passive"))
      (node (ref "D6") (pin "2") (pinfunction "K_2") (pintype "passive"))
      (node (ref "R13") (pin "1") (pinfunction "1_1") (pintype "passive"))
      (node (ref "R29") (pin "2") (pinfunction "2_2") (pintype "passive"))
      (node (ref "R35") (pin "2") (pinfunction "2_2") (pintype "passive"))
      (node (ref "U1") (pin "7") (pinfunction "VIN_7") (pintype "passive"))
    )
    (net (code "100") (name "VDD3V3") (class "Default")
      (node (ref "C41") (pin "2") (pinfunction "2_2") (pintype "passive"))
      (node (ref "U10") (pin "26") (pinfunction "VDD_SDIO_26") (pintype "passive"))
    )
    (net (code "101") (name "unconnected-(J3-Pad4)") (class "Default")
      (node (ref "J3") (pin "4") (pinfunction "4_4") (pintype "passive+no_connect"))
    )
    (net (code "102") (name "unconnected-(J3-Pad5)") (class "Default")
      (node (ref "J3") (pin "5") (pinfunction "5_5") (pintype "passive+no_connect"))
    )
    (net (code "103") (name "unconnected-(J3-Pad6)") (class "Default")
      (node (ref "J3") (pin "6") (pinfunction "6_6") (pintype "passive+no_connect"))
    )
    (net (code "104") (name "unconnected-(J3-Pad7)") (class "Default")
      (node (ref "J3") (pin "7") (pinfunction "7_7") (pintype "passive+no_connect"))
    )
    (net (code "105") (name "unconnected-(J3-Pad8)") (class "Default")
      (node (ref "J3") (pin "8") (pinfunction "8_8") (pintype "passive+no_connect"))
    )
    (net (code "106") (name "unconnected-(J3-Pad9)") (class "Default")
      (node (ref "J3") (pin "9") (pinfunction "9_9") (pintype "passive+no_connect"))
    )
    (net (code "107") (name "unconnected-(J3-Pad17)") (class "Default")
      (node (ref "J3") (pin "17") (pinfunction "17_17") (pintype "passive+no_connect"))
    )
    (net (code "108") (name "unconnected-(J3-Pad18)") (class "Default")
      (node (ref "J3") (pin "18") (pinfunction "18_18") (pintype "passive+no_connect"))
    )
    (net (code "109") (name "unconnected-(J3-Pad19)") (class "Default")
      (node (ref "J3") (pin "19") (pinfunction "19_19") (pintype "passive+no_connect"))
    )
    (net (code "110") (name "unconnected-(J3-Pad20)") (class "Default")
      (node (ref "J3") (pin "20") (pinfunction "20_20") (pintype "passive+no_connect"))
    )
    (net (code "111") (name "unconnected-(SD-D1-Pad8)") (class "Default")
      (node (ref "SD") (pin "8") (pinfunction "D1_8") (pintype "passive"))
    )
    (net (code "112") (name "unconnected-(SD-D2-Pad1)") (class "Default")
      (node (ref "SD") (pin "1") (pinfunction "D2_1") (pintype "passive"))
    )
    (net (code "113") (name "unconnected-(U4-AP_CS-Pad12)") (class "Default")
      (node (ref "U4") (pin "12") (pinfunction "AP_CS_12") (pintype "passive"))
    )
    (net (code "114") (name "unconnected-(U4-AP_SDO{slash}AP_AD0-Pad1)") (class "Default")
      (node (ref "U4") (pin "1") (pinfunction "AP_SDO/AP_AD0_1") (pintype "passive"))
    )
    (net (code "115") (name "unconnected-(U4-INT1{slash}INT-Pad4)") (class "Default")
      (node (ref "U4") (pin "4") (pinfunction "INT1/INT_4") (pintype "passive"))
    )
    (net (code "116") (name "unconnected-(U4-INT2{slash}FSYNC-Pad9)") (class "Default")
      (node (ref "U4") (pin "9") (pinfunction "INT2/FSYNC_9") (pintype "passive"))
    )
    (net (code "117") (name "unconnected-(U4-RESV-Pad2)") (class "Default")
      (node (ref "U4") (pin "2") (pinfunction "RESV_2") (pintype "passive+no_connect"))
    )
    (net (code "118") (name "unconnected-(U4-RESV-Pad3)") (class "Default")
      (node (ref "U4") (pin "3") (pinfunction "RESV_3") (pintype "passive+no_connect"))
    )
    (net (code "119") (name "unconnected-(U4-RESV-Pad10)") (class "Default")
      (node (ref "U4") (pin "10") (pinfunction "RESV_10") (pintype "passive+no_connect"))
    )
    (net (code "120") (name "unconnected-(U4-RESV-Pad11)") (class "Default")
      (node (ref "U4") (pin "11") (pinfunction "RESV_11") (pintype "passive+no_connect"))
    )
    (net (code "121") (name "unconnected-(U5-CTS#-Pad9)") (class "Default")
      (node (ref "U5") (pin "9") (pinfunction "CTS#_9") (pintype "passive"))
    )
    (net (code "122") (name "unconnected-(U5-DCD#-Pad12)") (class "Default")
      (node (ref "U5") (pin "12") (pinfunction "DCD#_12") (pintype "passive"))
    )
    (net (code "123") (name "unconnected-(U5-DSR#-Pad10)") (class "Default")
      (node (ref "U5") (pin "10") (pinfunction "DSR#_10") (pintype "passive"))
    )
    (net (code "124") (name "unconnected-(U5-R232-Pad15)") (class "Default")
      (node (ref "U5") (pin "15") (pinfunction "R232_15") (pintype "passive"))
    )
    (net (code "125") (name "unconnected-(U5-RI-Pad11)") (class "Default")
      (node (ref "U5") (pin "11") (pinfunction "RI_11") (pintype "passive"))
    )
    (net (code "126") (name "unconnected-(U5-V3-Pad4)") (class "Default")
      (node (ref "U5") (pin "4") (pinfunction "V3_4") (pintype "passive"))
    )
    (net (code "127") (name "unconnected-(U6-CLKOUTSOF-Pad3)") (class "Default")
      (node (ref "U6") (pin "3") (pinfunction "CLKOUTSOF_3") (pintype "passive+no_connect"))
    )
    (net (code "128") (name "unconnected-(U6-RX0BF#-Pad11)") (class "Default")
      (node (ref "U6") (pin "11") (pinfunction "RX0BF#_11") (pintype "passive+no_connect"))
    )
    (net (code "129") (name "unconnected-(U6-RX1BF#-Pad10)") (class "Default")
      (node (ref "U6") (pin "10") (pinfunction "RX1BF#_10") (pintype "passive+no_connect"))
    )
    (net (code "130") (name "unconnected-(U6-TX0RTS#-Pad4)") (class "Default")
      (node (ref "U6") (pin "4") (pinfunction "TX0RTS#_4") (pintype "passive+no_connect"))
    )
    (net (code "131") (name "unconnected-(U6-TX1RTS#-Pad5)") (class "Default")
      (node (ref "U6") (pin "5") (pinfunction "TX1RTS#_5") (pintype "passive+no_connect"))
    )
    (net (code "132") (name "unconnected-(U6-TX2RTS#-Pad6)") (class "Default")
      (node (ref "U6") (pin "6") (pinfunction "TX2RTS#_6") (pintype "passive+no_connect"))
    )
    (net (code "133") (name "unconnected-(U7-VREF-Pad5)") (class "Default")
      (node (ref "U7") (pin "5") (pinfunction "VREF_5") (pintype "passive+no_connect"))
    )
  )
)
